# Power_Management.net
KiCad netlist of a schematic drawn in Altium Designer
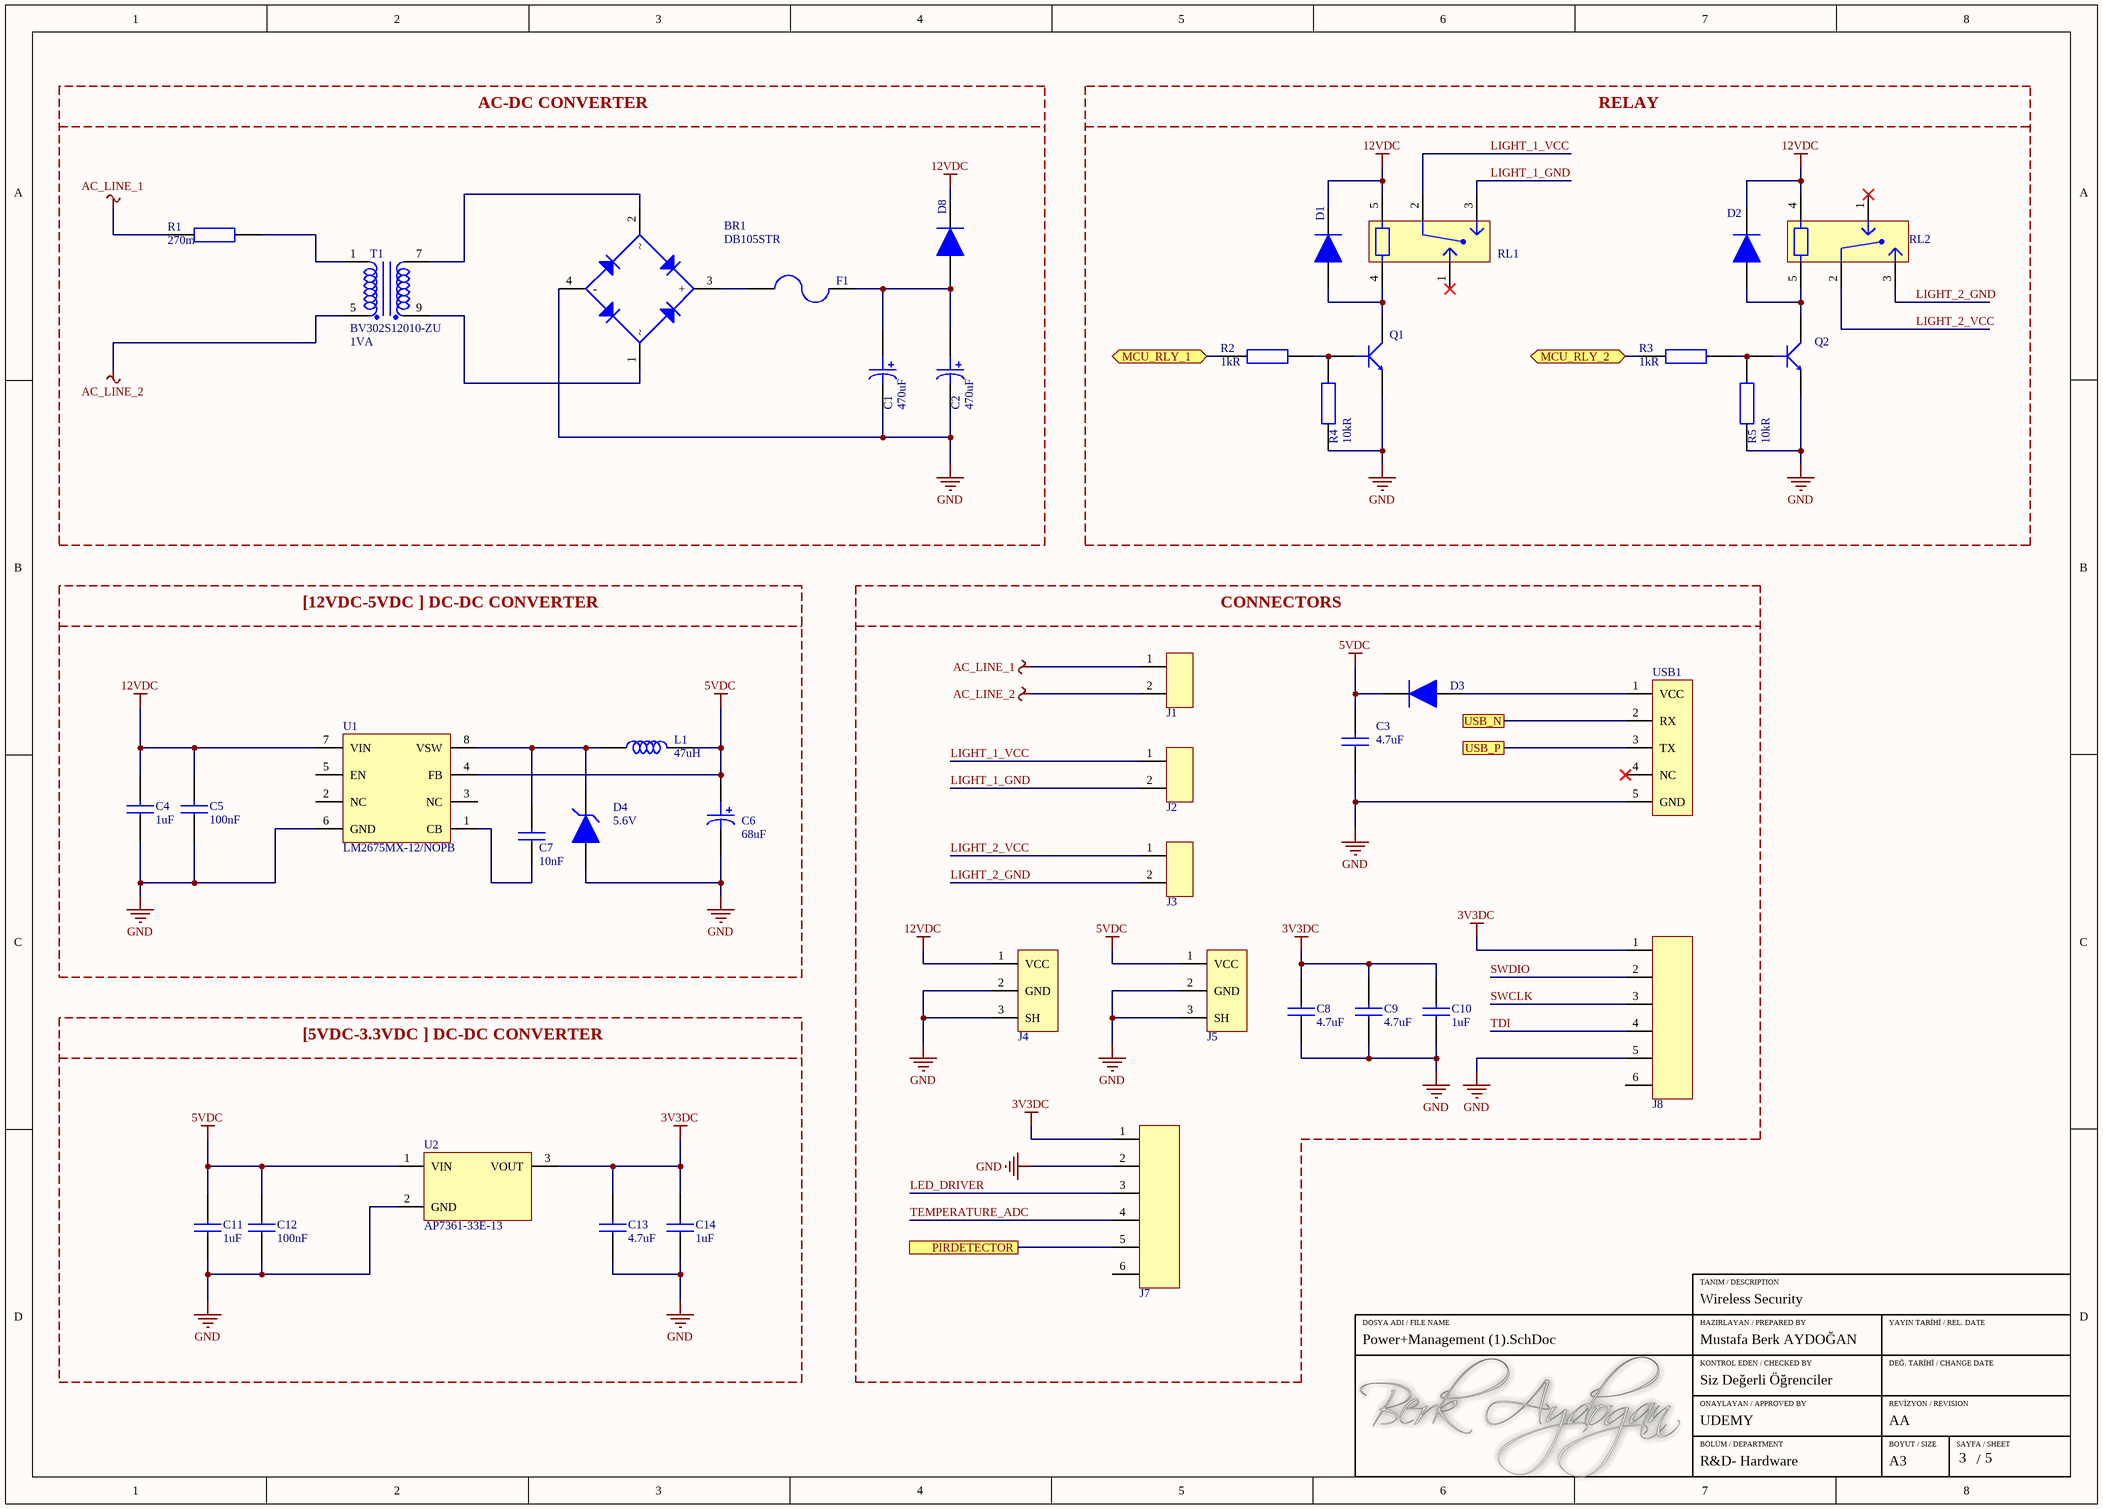
[diagram p0: Power+Management (1).SchDoc]

(export (version "E")
  (design (tool "Eeschema 10.0.6"))
  (components
    (comp (ref "BR1")
      (value "DB105STR")
      (footprint "DB105STR")
      (description "Bridge Diode AC-DC")
      (fields (field (name "MANUFACTURER") "Sangdest Microelectronics") (field (name "DESIGNED BY") "BERK"))
      (libsource (lib "UDEMY_Library") (part "DB105STR"))
    )
    (comp (ref "C1")
      (value "ESH477M050AH4AA")
      (footprint "CAP_RADIAL_D10_P5")
      (description "CAP ALU ELEC 470uF 50V RADIAL")
      (fields
        (field (name "MANUFACTURER") "KEMET")
        (field (name "TOLERANCE") "20%")
        (field (name "CAPACITANCE") "470uF")
        (field (name "DESIGNED BY") "BERK")
      )
      (libsource (lib "UDEMY_Library") (part "CAP ALU ELEC 470uF 50V"))
    )
    (comp (ref "C2")
      (value "ESH477M050AH4AA")
      (footprint "CAP_RADIAL_D10_P5")
      (description "CAP ALU ELEC 470uF 50V RADIAL")
      (fields
        (field (name "MANUFACTURER") "KEMET")
        (field (name "TOLERANCE") "20%")
        (field (name "CAPACITANCE") "470uF")
        (field (name "DESIGNED BY") "BERK")
      )
      (libsource (lib "UDEMY_Library") (part "CAP ALU ELEC 470uF 50V"))
    )
    (comp (ref "C3")
      (value "CL21A475KAQNNNE")
      (footprint "CAP_0805")
      (description "CAP CER 4.7uF %10 0805")
      (fields
        (field (name "MANUFACTURER") "Samsung")
        (field (name "TOLERANCE") "10%")
        (field (name "CAPACITANCE") "4.7uF")
        (field (name "DESIGNED BY") "BERK")
      )
      (libsource (lib "UDEMY_Library") (part "CAP CER 4.7uF 0805"))
    )
    (comp (ref "C4")
      (value "CL21B105KBFNNNE")
      (footprint "CAP_0805")
      (description "CAP CER 1uF %10 0805")
      (fields
        (field (name "MANUFACTURER") "Samsung")
        (field (name "TOLERANCE") "10%")
        (field (name "CAPACITANCE") "1uF")
        (field (name "DESIGNED BY") "BERK")
      )
      (libsource (lib "UDEMY_Library") (part "CAP CER 1uF 0805"))
    )
    (comp (ref "C5")
      (value "CL21B104KBCNNNC")
      (footprint "CAP_0805")
      (description "CAP CER 100nF %10 0805")
      (fields
        (field (name "MANUFACTURER") "Samsung")
        (field (name "TOLERANCE") "10%")
        (field (name "CAPACITANCE") "100nF")
        (field (name "DESIGNED BY") "BERK")
      )
      (libsource (lib "UDEMY_Library") (part "CAP CER 100nF 0805"))
    )
    (comp (ref "C6")
      (value "EEV686M035A9HAA")
      (footprint "CAP_EEVseries")
      (description "Cap Aluminum Lytic 68uF 35V 20% (6.3 X 7.7mm) SMD 280mA 2000h 105C T/R")
      (fields
        (field (name "MANUFACTURER") "KEMET")
        (field (name "TOLERANCE") "20%")
        (field (name "CAPACITANCE") "68uF")
      )
      (libsource (lib "UDEMY_Library") (part "CAP ALU 68uF"))
    )
    (comp (ref "C7")
      (value "0603B103K160CT")
      (footprint "CAP_0603")
      (description "CAP CER 10nF %10 0603")
      (fields
        (field (name "MANUFACTURER") "Walsin Technologies")
        (field (name "TOLERANCE") "10%")
        (field (name "CAPACITANCE") "10nF")
        (field (name "DESIGNED BY") "BERK")
      )
      (libsource (lib "UDEMY_Library") (part "CAP CER 10nF 0603"))
    )
    (comp (ref "C8")
      (value "CL21A475KAQNNNE")
      (footprint "CAP_0805")
      (description "CAP CER 4.7uF %10 0805")
      (fields
        (field (name "MANUFACTURER") "Samsung")
        (field (name "TOLERANCE") "10%")
        (field (name "CAPACITANCE") "4.7uF")
        (field (name "DESIGNED BY") "BERK")
      )
      (libsource (lib "UDEMY_Library") (part "CAP CER 4.7uF 0805"))
    )
    (comp (ref "C9")
      (value "CL21A475KAQNNNE")
      (footprint "CAP_0805")
      (description "CAP CER 4.7uF %10 0805")
      (fields
        (field (name "MANUFACTURER") "Samsung")
        (field (name "TOLERANCE") "10%")
        (field (name "CAPACITANCE") "4.7uF")
        (field (name "DESIGNED BY") "BERK")
      )
      (libsource (lib "UDEMY_Library") (part "CAP CER 4.7uF 0805"))
    )
    (comp (ref "C10")
      (value "CL21B105KBFNNNE")
      (footprint "CAP_0805")
      (description "CAP CER 1uF %10 0805")
      (fields
        (field (name "MANUFACTURER") "Samsung")
        (field (name "TOLERANCE") "10%")
        (field (name "CAPACITANCE") "1uF")
        (field (name "DESIGNED BY") "BERK")
      )
      (libsource (lib "UDEMY_Library") (part "CAP CER 1uF 0805"))
    )
    (comp (ref "C11")
      (value "CL21B105KBFNNNE")
      (footprint "CAP_0805")
      (description "CAP CER 1uF %10 0805")
      (fields
        (field (name "MANUFACTURER") "Samsung")
        (field (name "TOLERANCE") "10%")
        (field (name "CAPACITANCE") "1uF")
        (field (name "DESIGNED BY") "BERK")
      )
      (libsource (lib "UDEMY_Library") (part "CAP CER 1uF 0805"))
    )
    (comp (ref "C12")
      (value "C0603C104K5RACTU")
      (footprint "CAP_0603")
      (description "CAP CER 100nF %10 0603 SMD")
      (fields
        (field (name "MANUFACTURER") "KEMET")
        (field (name "TOLERANCE") "10%")
        (field (name "CAPACITANCE") "100nF")
        (field (name "DESIGNED BY") "BERK")
      )
      (libsource (lib "UDEMY_Library") (part "CAP CER 100nF 0603"))
    )
    (comp (ref "C13")
      (value "CL21A475KAQNNNE")
      (footprint "CAP_0805")
      (description "CAP CER 4.7uF %10 0805")
      (fields
        (field (name "MANUFACTURER") "Samsung")
        (field (name "TOLERANCE") "10%")
        (field (name "CAPACITANCE") "4.7uF")
        (field (name "DESIGNED BY") "BERK")
      )
      (libsource (lib "UDEMY_Library") (part "CAP CER 4.7uF 0805"))
    )
    (comp (ref "C14")
      (value "CL21B105KBFNNNE")
      (footprint "CAP_0805")
      (description "CAP CER 1uF %10 0805")
      (fields
        (field (name "MANUFACTURER") "Samsung")
        (field (name "TOLERANCE") "10%")
        (field (name "CAPACITANCE") "1uF")
        (field (name "DESIGNED BY") "BERK")
      )
      (libsource (lib "UDEMY_Library") (part "CAP CER 1uF 0805"))
    )
    (comp (ref "D1")
      (value "1N4148WS")
      (footprint "SOD323F")
      (description "Diode, Single, 75 V, 150 mA, 1 V, 4 ns")
      (fields
        (field (name "MANUFACTURER") "ON Semiconductor / Fairchild")
        (field (name "DESIGNED BY") "BERK")
      )
      (libsource (lib "UDEMY_Library") (part "1N4148WS"))
    )
    (comp (ref "D2")
      (value "1N4148WS")
      (footprint "SOD323F")
      (description "Diode, Single, 75 V, 150 mA, 1 V, 4 ns")
      (fields
        (field (name "MANUFACTURER") "ON Semiconductor / Fairchild")
        (field (name "DESIGNED BY") "BERK")
      )
      (libsource (lib "UDEMY_Library") (part "1N4148WS"))
    )
    (comp (ref "D3")
      (value "1N4148WS")
      (footprint "SOD323F")
      (description "Diode, Single, 75 V, 150 mA, 1 V, 4 ns")
      (fields
        (field (name "MANUFACTURER") "ON Semiconductor / Fairchild")
        (field (name "DESIGNED BY") "BERK")
      )
      (libsource (lib "UDEMY_Library") (part "1N4148WS"))
    )
    (comp (ref "D4")
      (value "1SMB5919BT3G")
      (footprint "SMB")
      (description "Diode Zener Single 5.6V 5% 3W 2-Pin SMB T/R")
      (fields
        (field (name "MANUFACTURER") "ON Semiconductor")
        (field (name "TOLERANCE") "5%")
        (field (name "WORKING VOLTAGE") "5.6V")
        (field (name "DESIGNED BY") "BERK")
      )
      (libsource (lib "UDEMY_Library") (part "1SMB5919BT3G"))
    )
    (comp (ref "D8")
      (value "1N4148WS")
      (footprint "SOD323F")
      (description "Diode, Single, 75 V, 150 mA, 1 V, 4 ns")
      (fields
        (field (name "MANUFACTURER") "ON Semiconductor / Fairchild")
        (field (name "DESIGNED BY") "BERK")
      )
      (libsource (lib "UDEMY_Library") (part "1N4148WS"))
    )
    (comp (ref "F1")
      (value "3413.0216.22")
      (footprint "3413.0216.22")
      (description "FUSE BRD MNT 1A 32VAC 63VDC 1206")
      (fields (field (name "MANUFACTURER") "Schurter") (field (name "DESIGNED BY") "BERK"))
      (libsource (lib "UDEMY_Library") (part "FUSE 3413.0216.22"))
    )
    (comp (ref "J1")
      (value "TBP01R1-508-02BE")
      (footprint "TBP01R1-508")
      (description "Conn Shrouded Header HDR 2 POS 5.08mm Solder RA Side Entry Thru-Hole Bag")
      (fields (field (name "MANUFACTURER") "CUI") (field (name "DESIGNED BY") "BERK"))
      (libsource (lib "UDEMY_Library") (part "TBP01R1-508-02BE"))
    )
    (comp (ref "J2")
      (value "TBP01R1-508-02BE")
      (footprint "TBP01R1-508")
      (description "Conn Shrouded Header HDR 2 POS 5.08mm Solder RA Side Entry Thru-Hole Bag")
      (fields (field (name "MANUFACTURER") "CUI") (field (name "DESIGNED BY") "BERK"))
      (libsource (lib "UDEMY_Library") (part "TBP01R1-508-02BE"))
    )
    (comp (ref "J3")
      (value "TBP01R1-508-02BE")
      (footprint "TBP01R1-508")
      (description "Conn Shrouded Header HDR 2 POS 5.08mm Solder RA Side Entry Thru-Hole Bag")
      (fields (field (name "MANUFACTURER") "CUI") (field (name "DESIGNED BY") "BERK"))
      (libsource (lib "UDEMY_Library") (part "TBP01R1-508-02BE"))
    )
    (comp (ref "J4")
      (value "PJ-037AH-SMT-TR")
      (footprint "JACK")
      (description "DC Power Connectors Power Jacks")
      (fields (field (name "MANUFACTURER") "CUI") (field (name "DESIGNED BY") "BERK"))
      (libsource (lib "UDEMY_Library") (part "PJ-037AH-SMT-TR"))
    )
    (comp (ref "J5")
      (value "PJ-037AH-SMT-TR")
      (footprint "JACK")
      (description "DC Power Connectors Power Jacks")
      (fields (field (name "MANUFACTURER") "CUI") (field (name "DESIGNED BY") "BERK"))
      (libsource (lib "UDEMY_Library") (part "PJ-037AH-SMT-TR"))
    )
    (comp (ref "J7")
      (value "64800611622")
      (footprint "64800611622")
      (description "1.50mm 6PIN Connector")
      (fields (field (name "MANUFACTURER") "Wurth Electronics"))
      (libsource (lib "UDEMY_Library") (part "64800611622_conn_6pin"))
    )
    (comp (ref "J8")
      (value "64800611622")
      (footprint "64800611622")
      (description "1.50mm 6PIN Connector")
      (fields (field (name "MANUFACTURER") "Wurth Electronics"))
      (libsource (lib "UDEMY_Library") (part "64800611622_conn_6pin"))
    )
    (comp (ref "L1")
      (value "78438335470")
      (footprint "IND_1212")
      (description "FIXED IND 47UH 390MA 2.3 OHM SMD")
      (fields
        (field (name "MANUFACTURER") "Wurth Electronics")
        (field (name "TOLERANCE") "30%")
        (field (name "INDUCTANCE") "47uH")
        (field (name "DESIGNED BY") "BERK")
      )
      (libsource (lib "UDEMY_Library") (part "IND 47uH"))
    )
    (comp (ref "Q1")
      (value "MMBT3904-7-F")
      (footprint "SOT-23F")
      (description "Transistor General Purpose BJT NPN 40 Volt 0.2A Automotive 3-Pin SOT-23")
      (fields (field (name "MANUFACTURER") "Diodes Zetex") (field (name "DESIGNED BY") "BERK"))
      (libsource (lib "UDEMY_Library") (part "MMBT3904-7-F"))
    )
    (comp (ref "Q2")
      (value "MMBT3904-7-F")
      (footprint "SOT-23F")
      (description "Transistor General Purpose BJT NPN 40 Volt 0.2A Automotive 3-Pin SOT-23")
      (fields (field (name "MANUFACTURER") "Diodes Zetex") (field (name "DESIGNED BY") "BERK"))
      (libsource (lib "UDEMY_Library") (part "MMBT3904-7-F"))
    )
    (comp (ref "R1")
      (value "5WD27")
      (footprint "RES_AXIAL_W")
      (description "Resistor 5 Watt Cermet Wirewound Flameproof .27 Ohm 5% Axial Lead")
      (fields
        (field (name "MANUFACTURER") "NTE Electronics")
        (field (name "TOLERANCE") "5%")
        (field (name "RESISTANCE") "270m")
        (field (name "DESIGNED BY") "BERK")
      )
      (libsource (lib "UDEMY_Library") (part "5WD27"))
    )
    (comp (ref "R2")
      (value "RC0603FR-0710KL")
      (footprint "RES_0603")
      (description "RES 1K %1 OHM 0603 SMD")
      (fields
        (field (name "MANUFACTURER") "Yageo")
        (field (name "MANUFACTURER PART NUMBER") "RC0603JR-071KL")
        (field (name "RESISTANCE") "1kR")
        (field (name "DESIGNED BY") "BERK")
      )
      (libsource (lib "UDEMY_Library") (part "RES 1K OHM 0603"))
    )
    (comp (ref "R3")
      (value "RC0603FR-0710KL")
      (footprint "RES_0603")
      (description "RES 1K %1 OHM 0603 SMD")
      (fields
        (field (name "MANUFACTURER") "Yageo")
        (field (name "MANUFACTURER PART NUMBER") "RC0603JR-071KL")
        (field (name "RESISTANCE") "1kR")
        (field (name "DESIGNED BY") "BERK")
      )
      (libsource (lib "UDEMY_Library") (part "RES 1K OHM 0603"))
    )
    (comp (ref "R4")
      (value "RC0603FR-0710KL")
      (footprint "RES_0603")
      (description "RES 10K %1 OHM 0603 SMD")
      (fields
        (field (name "MANUFACTURER") "Yageo")
        (field (name "TOLERANCE") "1%")
        (field (name "RESISTANCE") "10kR")
        (field (name "DESIGNED BY") "BERK")
      )
      (libsource (lib "UDEMY_Library") (part "RES 10K OHM 0603"))
    )
    (comp (ref "R5")
      (value "RC0603FR-0710KL")
      (footprint "RES_0603")
      (description "RES 10K %1 OHM 0603 SMD")
      (fields
        (field (name "MANUFACTURER") "Yageo")
        (field (name "TOLERANCE") "1%")
        (field (name "RESISTANCE") "10kR")
        (field (name "DESIGNED BY") "BERK")
      )
      (libsource (lib "UDEMY_Library") (part "RES 10K OHM 0603"))
    )
    (comp (ref "RL1")
      (value "ALQ112")
      (footprint "ALQ112")
      (description "General Purpose Relay SPDT (1 Form C) 12VDC Coil Through Hole")
      (fields (field (name "MANUFACTURER") "Panasonic") (field (name "DESIGNED BY") "BERK"))
      (libsource (lib "UDEMY_Library") (part "ALQ112"))
    )
    (comp (ref "RL2")
      (value "ALQ112")
      (footprint "ALQ112")
      (description "General Purpose Relay SPDT (1 Form C) 12VDC Coil Through Hole")
      (fields (field (name "MANUFACTURER") "Panasonic") (field (name "DESIGNED BY") "BERK"))
      (libsource (lib "") (part "ALQ112_1"))
    )
    (comp (ref "T1")
      (value "BV302S12010-ZU")
      (footprint "BV302S")
      (description "230-12 Transformer 1VA")
      (fields
        (field (name "MANUFACTURER") "Zettler Magnetics")
        (field (name "RATED POWER") "1VA")
        (field (name "DESIGNED BY") "BERK")
      )
      (libsource (lib "UDEMY_Library") (part "BV302S12010-ZU"))
    )
    (comp (ref "U1")
      (value "LM2675MX-12/NOPB")
      (footprint "SOIC8")
      (description "Switching Voltage Regulators Pwr Cnvtr Hi Eff 1A SD Vtg Reg")
      (fields (field (name "MANUFACTURER") "TI National Semiconductor") (field (name "DESIGNED BY") "BERK"))
      (libsource (lib "UDEMY_Library") (part "LM2675MX-12/NOPB"))
    )
    (comp (ref "U2")
      (value "AP7361-33E-13")
      (footprint "SOT223")
      (description "LDO Regulator Pos 3.3V 1A 4-Pin(3+Tab) SOT-223 T/R")
      (fields (field (name "MANUFACTURER") "Diodes") (field (name "DESIGNED BY") "BERK"))
      (libsource (lib "UDEMY_Library") (part "AP7361-33E-13"))
    )
    (comp (ref "USB1")
      (value "10118192-0001LF")
      (footprint "MICRO_B_USB")
      (description "CONN RCPT USB2.0 MICRO B SMD R/A")
      (fields (field (name "MANUFACTURER") "Amphenol FCI") (field (name "DESIGNED BY") "BERK"))
      (libsource (lib "UDEMY_Library") (part "Micro B USB Connector"))
    )
  )
  (nets
    (net (code "1") (name "/LED_DRIVER") (class "Default") (node (ref "J7") (pin "3") (pintype "power_in")))
    (net (code "2") (name "/LIGHT_1_GND") (class "Default")
      (node (ref "J2") (pin "2") (pinfunction "2_2") (pintype "power_in"))
      (node (ref "RL1") (pin "3") (pinfunction "3_3") (pintype "passive"))
    )
    (net (code "3") (name "/LIGHT_1_VCC") (class "Default")
      (node (ref "J2") (pin "1") (pinfunction "1_1") (pintype "power_in"))
      (node (ref "RL1") (pin "2") (pinfunction "2_2") (pintype "passive"))
    )
    (net (code "4") (name "/LIGHT_2_GND") (class "Default")
      (node (ref "J3") (pin "2") (pinfunction "2_2") (pintype "power_in"))
      (node (ref "RL2") (pin "3") (pinfunction "3_3") (pintype "passive"))
    )
    (net (code "5") (name "/LIGHT_2_VCC") (class "Default")
      (node (ref "J3") (pin "1") (pinfunction "1_1") (pintype "power_in"))
      (node (ref "RL2") (pin "2") (pinfunction "2_2") (pintype "passive"))
    )
    (net (code "6") (name "/MCU_RLY_1") (class "Default")
      (node (ref "R2") (pin "1") (pinfunction "1_1") (pintype "passive"))
    )
    (net (code "7") (name "/MCU_RLY_2") (class "Default")
      (node (ref "R3") (pin "1") (pinfunction "1_1") (pintype "passive"))
    )
    (net (code "8") (name "/PIRDETECTOR") (class "Default") (node (ref "J7") (pin "5") (pintype "power_in")))
    (net (code "9") (name "/SWCLK") (class "Default") (node (ref "J8") (pin "3") (pintype "power_in")))
    (net (code "10") (name "/SWDIO") (class "Default") (node (ref "J8") (pin "2") (pintype "power_in")))
    (net (code "11") (name "/TDI") (class "Default") (node (ref "J8") (pin "4") (pintype "power_in")))
    (net (code "12") (name "/TEMPERATURE_ADC") (class "Default")
      (node (ref "J7") (pin "4") (pintype "power_in"))
    )
    (net (code "13") (name "/USB_N") (class "Default")
      (node (ref "USB1") (pin "2") (pinfunction "RX_2") (pintype "power_in"))
    )
    (net (code "14") (name "/USB_P") (class "Default")
      (node (ref "USB1") (pin "3") (pinfunction "TX_3") (pintype "power_in"))
    )
    (net (code "15") (name "3V3DC") (class "Default")
      (node (ref "C10") (pin "2") (pinfunction "2_2") (pintype "passive"))
      (node (ref "C13") (pin "2") (pinfunction "2_2") (pintype "passive"))
      (node (ref "C14") (pin "2") (pinfunction "2_2") (pintype "passive"))
      (node (ref "C8") (pin "2") (pinfunction "2_2") (pintype "passive"))
      (node (ref "C9") (pin "2") (pinfunction "2_2") (pintype "passive"))
      (node (ref "J7") (pin "1") (pintype "power_in"))
      (node (ref "J8") (pin "1") (pintype "power_in"))
      (node (ref "U2") (pin "3") (pinfunction "VOUT_3") (pintype "passive"))
    )
    (net (code "16") (name "5VDC") (class "Default")
      (node (ref "C11") (pin "2") (pinfunction "2_2") (pintype "passive"))
      (node (ref "C12") (pin "2") (pinfunction "2_2") (pintype "passive"))
      (node (ref "C3") (pin "2") (pinfunction "2_2") (pintype "passive"))
      (node (ref "C6") (pin "1") (pinfunction "1_1") (pintype "passive"))
      (node (ref "D3") (pin "1") (pinfunction "1_1") (pintype "power_in"))
      (node (ref "J5") (pin "1") (pinfunction "VCC_1") (pintype "power_in"))
      (node (ref "L1") (pin "2") (pinfunction "2_2") (pintype "passive"))
      (node (ref "U1") (pin "4") (pinfunction "FB_4") (pintype "passive"))
      (node (ref "U2") (pin "1") (pinfunction "VIN_1") (pintype "passive"))
    )
    (net (code "17") (name "12VDC") (class "Default")
      (node (ref "C4") (pin "2") (pinfunction "2_2") (pintype "passive"))
      (node (ref "C5") (pin "2") (pinfunction "2_2") (pintype "passive"))
      (node (ref "D1") (pin "1") (pinfunction "1_1") (pintype "power_in"))
      (node (ref "D2") (pin "1") (pinfunction "1_1") (pintype "power_in"))
      (node (ref "D8") (pin "1") (pinfunction "1_1") (pintype "power_in"))
      (node (ref "J4") (pin "1") (pinfunction "VCC_1") (pintype "power_in"))
      (node (ref "RL1") (pin "5") (pinfunction "5_5") (pintype "passive"))
      (node (ref "RL2") (pin "4") (pinfunction "4_4") (pintype "passive"))
      (node (ref "U1") (pin "7") (pinfunction "VIN_7") (pintype "passive"))
    )
    (net (code "18") (name "AC_LINE_1") (class "Default")
      (node (ref "J1") (pin "1") (pinfunction "1_1") (pintype "power_in"))
      (node (ref "R1") (pin "1") (pinfunction "1_1") (pintype "passive"))
    )
    (net (code "19") (name "AC_LINE_2") (class "Default")
      (node (ref "J1") (pin "2") (pinfunction "2_2") (pintype "power_in"))
      (node (ref "T1") (pin "5") (pinfunction "5_5") (pintype "passive"))
    )
    (net (code "20") (name "GND") (class "Default")
      (node (ref "BR1") (pin "4") (pinfunction "-_4") (pintype "passive"))
      (node (ref "C1") (pin "2") (pinfunction "2_2") (pintype "passive"))
      (node (ref "C10") (pin "1") (pinfunction "1_1") (pintype "passive"))
      (node (ref "C11") (pin "1") (pinfunction "1_1") (pintype "passive"))
      (node (ref "C12") (pin "1") (pinfunction "1_1") (pintype "passive"))
      (node (ref "C13") (pin "1") (pinfunction "1_1") (pintype "passive"))
      (node (ref "C14") (pin "1") (pinfunction "1_1") (pintype "passive"))
      (node (ref "C2") (pin "2") (pinfunction "2_2") (pintype "passive"))
      (node (ref "C3") (pin "1") (pinfunction "1_1") (pintype "passive"))
      (node (ref "C4") (pin "1") (pinfunction "1_1") (pintype "passive"))
      (node (ref "C5") (pin "1") (pinfunction "1_1") (pintype "passive"))
      (node (ref "C6") (pin "2") (pinfunction "2_2") (pintype "passive"))
      (node (ref "C8") (pin "1") (pinfunction "1_1") (pintype "passive"))
      (node (ref "C9") (pin "1") (pinfunction "1_1") (pintype "passive"))
      (node (ref "D4") (pin "A") (pinfunction "A_A") (pintype "passive"))
      (node (ref "J4") (pin "2") (pinfunction "GND_2") (pintype "power_in"))
      (node (ref "J4") (pin "3") (pinfunction "SH_3") (pintype "power_in"))
      (node (ref "J5") (pin "2") (pinfunction "GND_2") (pintype "power_in"))
      (node (ref "J5") (pin "3") (pinfunction "SH_3") (pintype "power_in"))
      (node (ref "J7") (pin "2") (pintype "power_in"))
      (node (ref "J8") (pin "5") (pintype "power_in"))
      (node (ref "Q1") (pin "2") (pinfunction "E_2") (pintype "power_in"))
      (node (ref "Q2") (pin "2") (pinfunction "E_2") (pintype "power_in"))
      (node (ref "R4") (pin "1") (pinfunction "1_1") (pintype "passive"))
      (node (ref "R5") (pin "1") (pinfunction "1_1") (pintype "passive"))
      (node (ref "U1") (pin "6") (pinfunction "GND_6") (pintype "passive"))
      (node (ref "U2") (pin "2") (pinfunction "GND_2") (pintype "passive"))
      (node (ref "USB1") (pin "5") (pinfunction "GND_5") (pintype "power_in"))
    )
    (net (code "21") (name "Net-(BR1-+)") (class "Default")
      (node (ref "BR1") (pin "3") (pinfunction "+_3") (pintype "passive"))
      (node (ref "F1") (pin "1") (pinfunction "1_1") (pintype "passive"))
    )
    (net (code "22") (name "Net-(BR1-~-Pad1)") (class "Default")
      (node (ref "BR1") (pin "1") (pinfunction "~_1") (pintype "passive"))
      (node (ref "T1") (pin "9") (pinfunction "9_9") (pintype "passive"))
    )
    (net (code "23") (name "Net-(BR1-~-Pad2)") (class "Default")
      (node (ref "BR1") (pin "2") (pinfunction "~_2") (pintype "passive"))
      (node (ref "T1") (pin "7") (pinfunction "7_7") (pintype "passive"))
    )
    (net (code "24") (name "Net-(C1-Pad1)") (class "Default")
      (node (ref "C1") (pin "1") (pinfunction "1_1") (pintype "passive"))
      (node (ref "C2") (pin "1") (pinfunction "1_1") (pintype "passive"))
      (node (ref "D8") (pin "2") (pinfunction "2_2") (pintype "power_in"))
      (node (ref "F1") (pin "2") (pinfunction "2_2") (pintype "passive"))
    )
    (net (code "25") (name "Net-(Q1-B)") (class "Default")
      (node (ref "Q1") (pin "1") (pinfunction "B_1") (pintype "power_in"))
      (node (ref "R2") (pin "2") (pinfunction "2_2") (pintype "passive"))
      (node (ref "R4") (pin "2") (pinfunction "2_2") (pintype "passive"))
    )
    (net (code "26") (name "Net-(Q1-C)") (class "Default")
      (node (ref "D1") (pin "2") (pinfunction "2_2") (pintype "power_in"))
      (node (ref "Q1") (pin "3") (pinfunction "C_3") (pintype "power_in"))
      (node (ref "RL1") (pin "4") (pinfunction "4_4") (pintype "passive"))
    )
    (net (code "27") (name "Net-(Q2-B)") (class "Default")
      (node (ref "Q2") (pin "1") (pinfunction "B_1") (pintype "power_in"))
      (node (ref "R3") (pin "2") (pinfunction "2_2") (pintype "passive"))
      (node (ref "R5") (pin "2") (pinfunction "2_2") (pintype "passive"))
    )
    (net (code "28") (name "Net-(Q2-C)") (class "Default")
      (node (ref "D2") (pin "2") (pinfunction "2_2") (pintype "power_in"))
      (node (ref "Q2") (pin "3") (pinfunction "C_3") (pintype "power_in"))
      (node (ref "RL2") (pin "5") (pinfunction "5_5") (pintype "passive"))
    )
    (net (code "29") (name "Net-(R1-Pad2)") (class "Default")
      (node (ref "R1") (pin "2") (pinfunction "2_2") (pintype "passive"))
      (node (ref "T1") (pin "1") (pinfunction "1_1") (pintype "passive"))
    )
    (net (code "30") (name "Net-(U1-CB)") (class "Default")
      (node (ref "C7") (pin "1") (pinfunction "1_1") (pintype "passive"))
      (node (ref "U1") (pin "1") (pinfunction "CB_1") (pintype "passive"))
    )
    (net (code "31") (name "Net-(U1-VSW)") (class "Default")
      (node (ref "C7") (pin "2") (pinfunction "2_2") (pintype "passive"))
      (node (ref "D4") (pin "C") (pinfunction "C_C") (pintype "passive"))
      (node (ref "L1") (pin "1") (pinfunction "1_1") (pintype "passive"))
      (node (ref "U1") (pin "8") (pinfunction "VSW_8") (pintype "passive"))
    )
    (net (code "32") (name "Net-(USB1-VCC)") (class "Default")
      (node (ref "D3") (pin "2") (pinfunction "2_2") (pintype "power_in"))
      (node (ref "USB1") (pin "1") (pinfunction "VCC_1") (pintype "power_in"))
    )
    (net (code "33") (name "unconnected-(J7-Pad6)") (class "Default")
      (node (ref "J7") (pin "6") (pintype "power_in"))
    )
    (net (code "34") (name "unconnected-(J8-Pad6)") (class "Default")
      (node (ref "J8") (pin "6") (pintype "power_in"))
    )
    (net (code "35") (name "unconnected-(RL1-Pad1)") (class "Default")
      (node (ref "RL1") (pin "1") (pinfunction "1_1") (pintype "passive+no_connect"))
    )
    (net (code "36") (name "unconnected-(RL2-Pad1)") (class "Default")
      (node (ref "RL2") (pin "1") (pinfunction "1_1") (pintype "passive+no_connect"))
    )
    (net (code "37") (name "unconnected-(U1-EN-Pad5)") (class "Default")
      (node (ref "U1") (pin "5") (pinfunction "EN_5") (pintype "passive"))
    )
    (net (code "38") (name "unconnected-(U1-NC-Pad2)") (class "Default")
      (node (ref "U1") (pin "2") (pinfunction "NC_2") (pintype "passive"))
    )
    (net (code "39") (name "unconnected-(U1-NC-Pad3)") (class "Default")
      (node (ref "U1") (pin "3") (pinfunction "NC_3") (pintype "passive"))
    )
    (net (code "40") (name "unconnected-(USB1-NC-Pad4)") (class "Default")
      (node (ref "USB1") (pin "4") (pinfunction "NC_4") (pintype "power_in+no_connect"))
    )
  )
)
